# XXXX_468323_001_3.net
KiCad netlist of a schematic drawn in Altium Designer
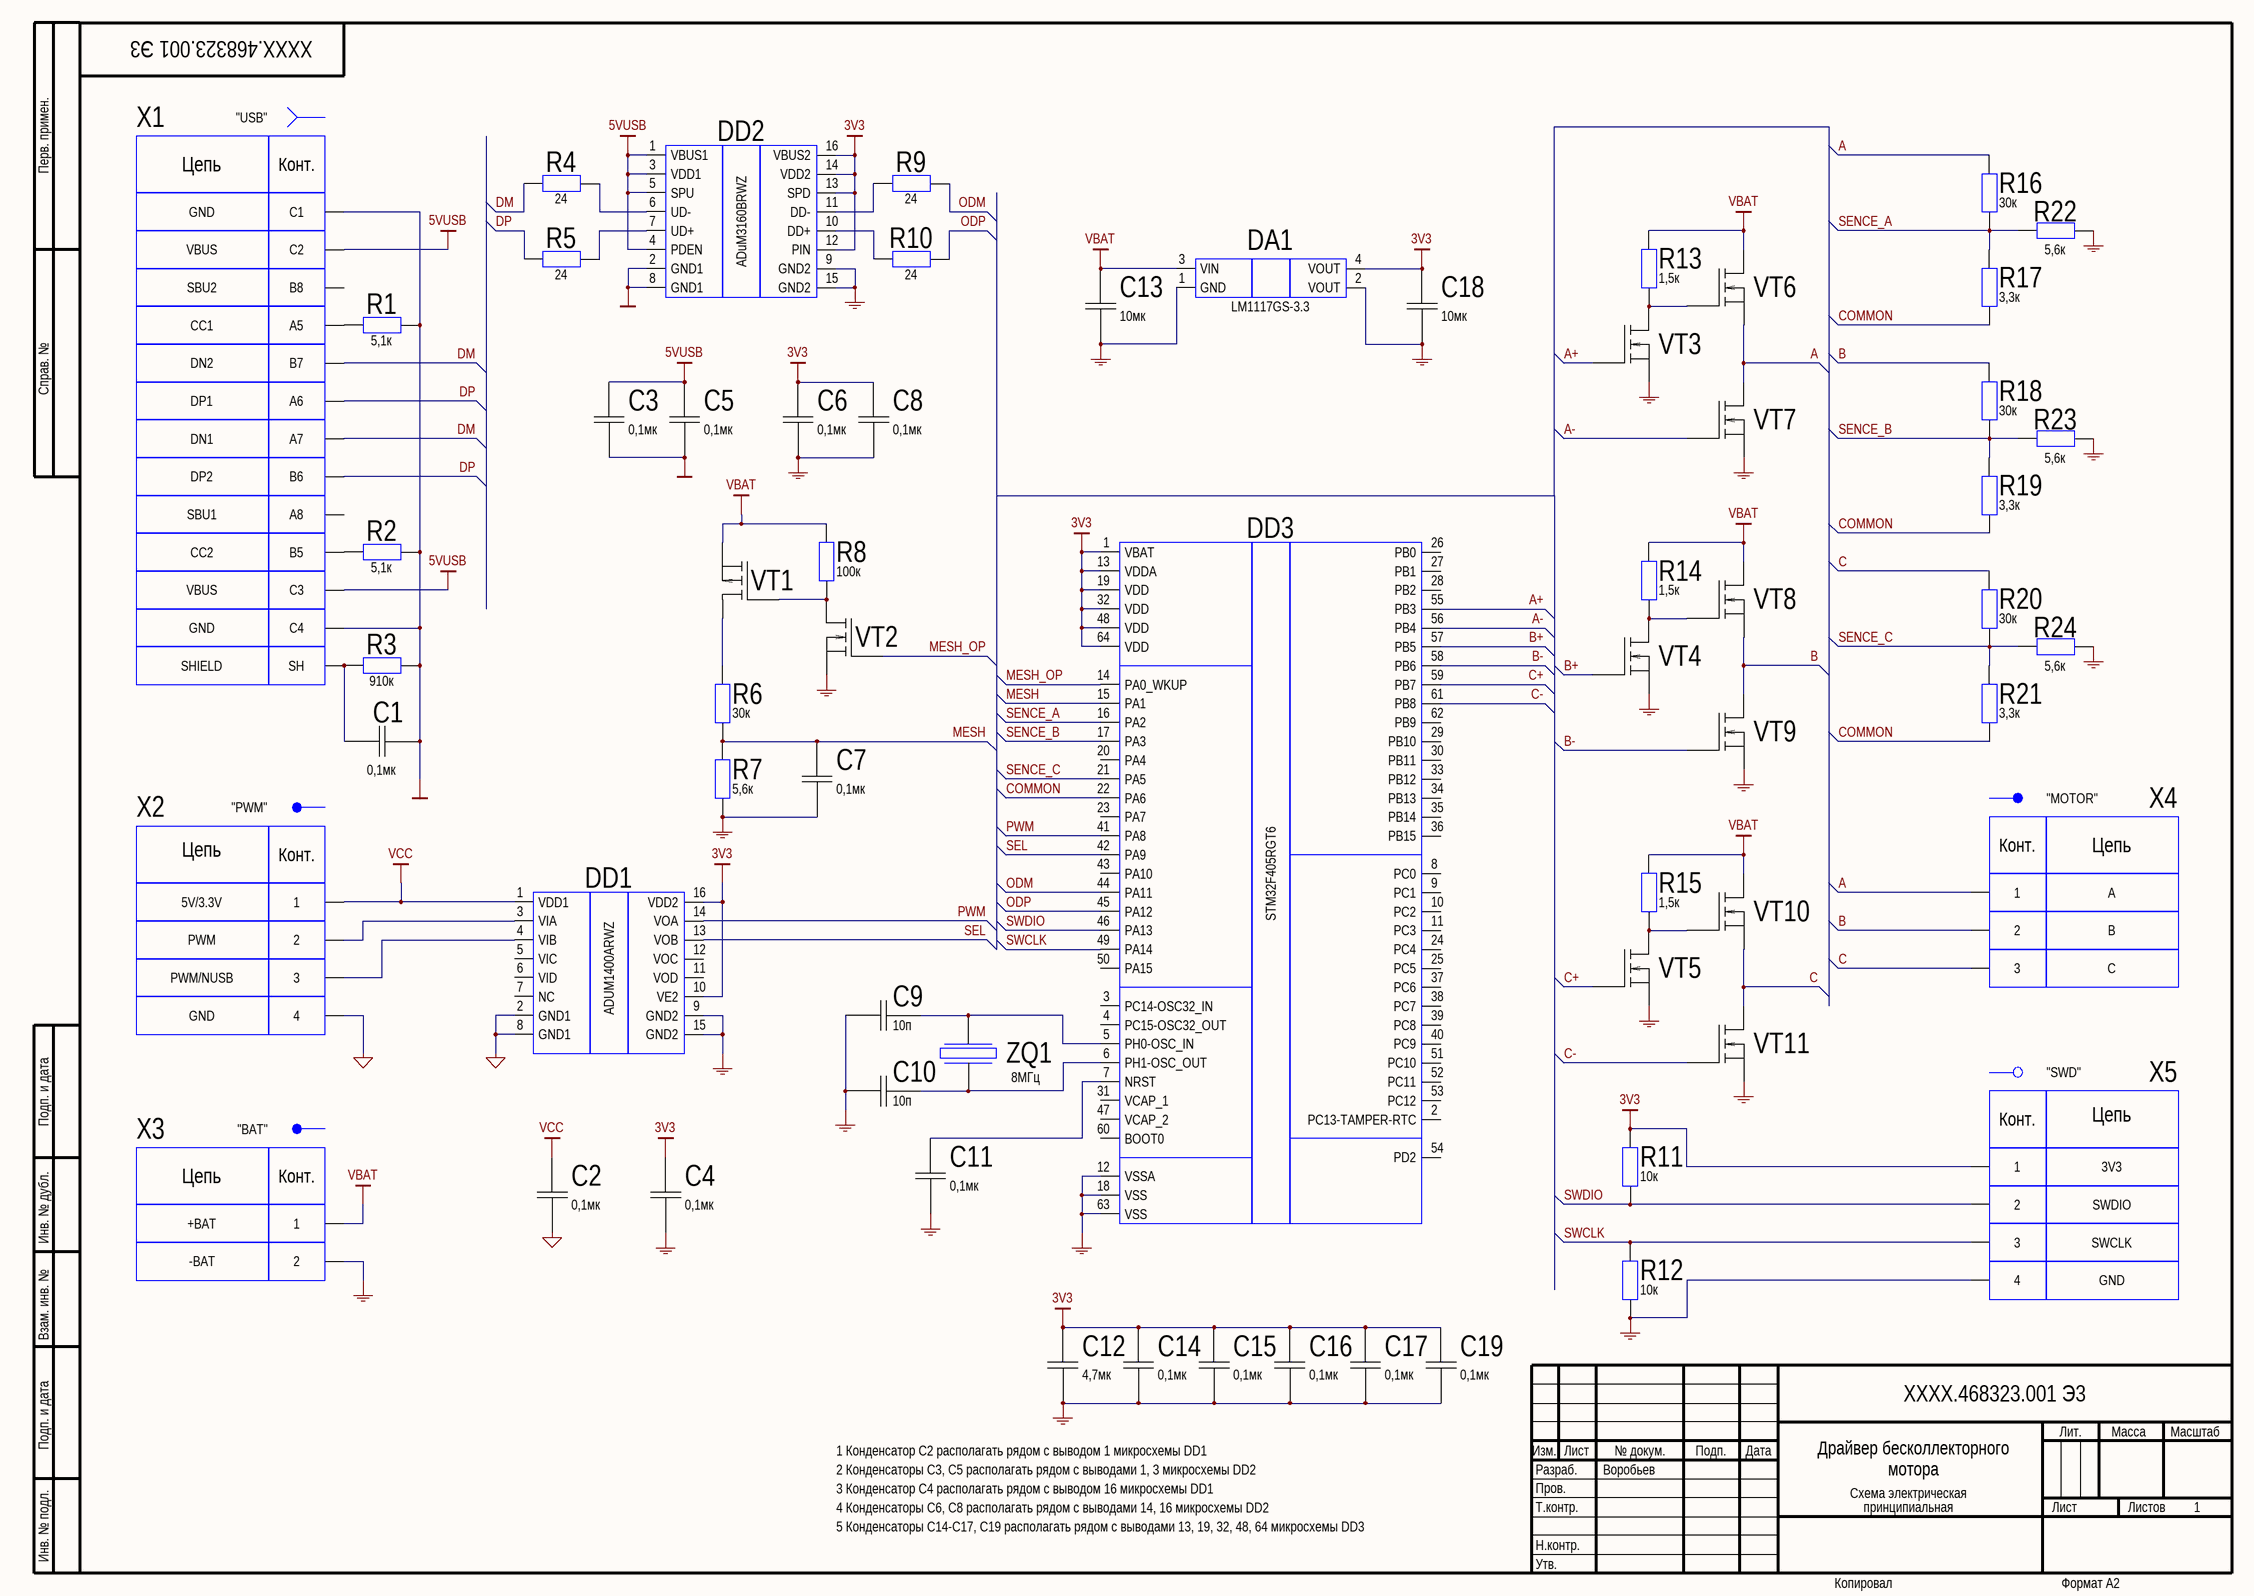
[diagram p0: XXXX.468323.001 Э3 Драйвер бесколлекторного мотора. Схема электрическая принципиальная.SchDoc]

(export (version "E")
  (design (tool "Eeschema 10.0.6"))
  (components
    (comp (ref "C1")
      (value "0,1мк")
      (footprint "CAPC1608X06L")
      (description "SMD0603 X7R 50 В, 0,1мкФ±10% CC0603KRX7R9BB104")
      (fields (field (name "PART NUMBER") "CC0603KRX7R9BB104") (field (name "VOLTAGE") "50 В"))
      (libsource (lib "Capacitors") (part "CAP"))
    )
    (comp (ref "C2")
      (value "0,1мк")
      (footprint "CAPC1608X06L")
      (description "SMD0603 X7R 50 В, 0,1мкФ±10% CC0603KRX7R9BB104")
      (fields (field (name "PART NUMBER") "CC0603KRX7R9BB104") (field (name "VOLTAGE") "50 В"))
      (libsource (lib "Capacitors") (part "CAP"))
    )
    (comp (ref "C3")
      (value "0,1мк")
      (footprint "CAPC1608X06L")
      (description "SMD0603 X7R 50 В, 0,1мкФ±10% CC0603KRX7R9BB104")
      (fields (field (name "PART NUMBER") "CC0603KRX7R9BB104") (field (name "VOLTAGE") "50 В"))
      (libsource (lib "Capacitors") (part "CAP"))
    )
    (comp (ref "C4")
      (value "0,1мк")
      (footprint "CAPC1608X06L")
      (description "SMD0603 X7R 50 В, 0,1мкФ±10% CC0603KRX7R9BB104")
      (fields (field (name "PART NUMBER") "CC0603KRX7R9BB104") (field (name "VOLTAGE") "50 В"))
      (libsource (lib "Capacitors") (part "CAP"))
    )
    (comp (ref "C5")
      (value "0,1мк")
      (footprint "CAPC1608X06L")
      (description "SMD0603 X7R 50 В, 0,1мкФ±10% CC0603KRX7R9BB104")
      (fields (field (name "PART NUMBER") "CC0603KRX7R9BB104") (field (name "VOLTAGE") "50 В"))
      (libsource (lib "Capacitors") (part "CAP"))
    )
    (comp (ref "C6")
      (value "0,1мк")
      (footprint "CAPC1608X06L")
      (description "SMD0603 X7R 50 В, 0,1мкФ±10% CC0603KRX7R9BB104")
      (fields (field (name "PART NUMBER") "CC0603KRX7R9BB104") (field (name "VOLTAGE") "50 В"))
      (libsource (lib "Capacitors") (part "CAP"))
    )
    (comp (ref "C7")
      (value "0,1мк")
      (footprint "CAPC1608X06L")
      (description "SMD0603 X7R 50 В, 0,1мкФ±10% CC0603KRX7R9BB104")
      (fields (field (name "PART NUMBER") "CC0603KRX7R9BB104") (field (name "VOLTAGE") "50 В"))
      (libsource (lib "Capacitors") (part "CAP"))
    )
    (comp (ref "C8")
      (value "0,1мк")
      (footprint "CAPC1608X06L")
      (description "SMD0603 X7R 50 В, 0,1мкФ±10% CC0603KRX7R9BB104")
      (fields (field (name "PART NUMBER") "CC0603KRX7R9BB104") (field (name "VOLTAGE") "50 В"))
      (libsource (lib "Capacitors") (part "CAP"))
    )
    (comp (ref "C9")
      (value "10п")
      (footprint "CAPC1608X06L")
      (description "SMD0603 NPO 50 В, 10пФ±5% CC0603JRNPO9BN100")
      (fields (field (name "PART NUMBER") "CC0603JRNPO9BN100") (field (name "VOLTAGE") "50 В"))
      (libsource (lib "Capacitors") (part "CAP"))
    )
    (comp (ref "C10")
      (value "10п")
      (footprint "CAPC1608X06L")
      (description "SMD0603 NPO 50 В, 10пФ±5% CC0603JRNPO9BN100")
      (fields (field (name "PART NUMBER") "CC0603JRNPO9BN100") (field (name "VOLTAGE") "50 В"))
      (libsource (lib "Capacitors") (part "CAP"))
    )
    (comp (ref "C11")
      (value "0,1мк")
      (footprint "CAPC1608X06L")
      (description "SMD0603 X7R 50 В, 0,1мкФ±10% CC0603KRX7R9BB104")
      (fields (field (name "PART NUMBER") "CC0603KRX7R9BB104") (field (name "VOLTAGE") "50 В"))
      (libsource (lib "Capacitors") (part "CAP"))
    )
    (comp (ref "C12")
      (value "4,7мк")
      (footprint "CAPC1608X06L")
      (description "SMD0603 X5R 6,3 В, 4,7мкФ±10% CC0603KRX5R5BB475")
      (fields (field (name "PART NUMBER") "CC0603KRX5R5BB475") (field (name "VOLTAGE") "6,3 В"))
      (libsource (lib "Capacitors") (part "CAP"))
    )
    (comp (ref "C13")
      (value "10мк")
      (footprint "CAPC3225X28N")
      (description "SMD1210 Y5R 50 В, 10мкФ±-20/+80% CC1210ZKY5V9BB106")
      (fields (field (name "PART NUMBER") "CC1210ZKY5V9BB106") (field (name "VOLTAGE") "50 В"))
      (libsource (lib "Capacitors") (part "CAP"))
    )
    (comp (ref "C14")
      (value "0,1мк")
      (footprint "CAPC1608X06L")
      (description "SMD0603 X7R 50 В, 0,1мкФ±10% CC0603KRX7R9BB104")
      (fields (field (name "PART NUMBER") "CC0603KRX7R9BB104") (field (name "VOLTAGE") "50 В"))
      (libsource (lib "Capacitors") (part "CAP"))
    )
    (comp (ref "C15")
      (value "0,1мк")
      (footprint "CAPC1608X06L")
      (description "SMD0603 X7R 50 В, 0,1мкФ±10% CC0603KRX7R9BB104")
      (fields (field (name "PART NUMBER") "CC0603KRX7R9BB104") (field (name "VOLTAGE") "50 В"))
      (libsource (lib "Capacitors") (part "CAP"))
    )
    (comp (ref "C16")
      (value "0,1мк")
      (footprint "CAPC1608X06L")
      (description "SMD0603 X7R 50 В, 0,1мкФ±10% CC0603KRX7R9BB104")
      (fields (field (name "PART NUMBER") "CC0603KRX7R9BB104") (field (name "VOLTAGE") "50 В"))
      (libsource (lib "Capacitors") (part "CAP"))
    )
    (comp (ref "C17")
      (value "0,1мк")
      (footprint "CAPC1608X06L")
      (description "SMD0603 X7R 50 В, 0,1мкФ±10% CC0603KRX7R9BB104")
      (fields (field (name "PART NUMBER") "CC0603KRX7R9BB104") (field (name "VOLTAGE") "50 В"))
      (libsource (lib "Capacitors") (part "CAP"))
    )
    (comp (ref "C18")
      (value "10мк")
      (footprint "CAPC1608X06L")
      (description "SMD0603 X5R 10 В, 10мкФ±10% CC0603KRX5R6BB106")
      (fields (field (name "PART NUMBER") "CC0603KRX5R6BB106") (field (name "VOLTAGE") "10 В"))
      (libsource (lib "Capacitors") (part "CAP"))
    )
    (comp (ref "C19")
      (value "0,1мк")
      (footprint "CAPC1608X06L")
      (description "SMD0603 X7R 50 В, 0,1мкФ±10% CC0603KRX7R9BB104")
      (fields (field (name "PART NUMBER") "CC0603KRX7R9BB104") (field (name "VOLTAGE") "50 В"))
      (libsource (lib "Capacitors") (part "CAP"))
    )
    (comp (ref "DA1")
      (value "LM1117GS-3.3")
      (footprint "SOT230P700X180-4N")
      (libsource (lib "IC") (part "LM1117GS-3.3"))
    )
    (comp (ref "DD1")
      (value "ADUM1400ARWZ")
      (footprint "SOP127P1030X265-16N")
      (libsource (lib "IC") (part "ADuM1400"))
    )
    (comp (ref "DD2")
      (value "ADuM3160BRWZ")
      (footprint "SOP127P1030X265-16N")
      (libsource (lib "IC") (part "ADuM3160"))
    )
    (comp (ref "DD3")
      (value "STM32F405RGT6")
      (footprint "TSQFP50P1200X1200X160-64N")
      (libsource (lib "IC") (part "STM32F405Rx"))
    )
    (comp (ref "R1")
      (value "5,1к")
      (footprint "RESC1608X06M")
      (description "SMD0603 0,1 Вт, 5,1 кОм±1% RC0603FR-075K1L")
      (fields (field (name "PART NUMBER") "RC0603FR-075K1L") (field (name "TOLERANCE") "1%"))
      (libsource (lib "") (part "RES_1"))
    )
    (comp (ref "R2")
      (value "5,1к")
      (footprint "RESC1608X06M")
      (description "SMD0603 0,1 Вт, 5,1 кОм±1% RC0603FR-075K1L")
      (fields (field (name "PART NUMBER") "RC0603FR-075K1L") (field (name "TOLERANCE") "1%"))
      (libsource (lib "") (part "RES_1"))
    )
    (comp (ref "R3")
      (value "910к")
      (footprint "RESC1608X06M")
      (description "SMD0603 0,1 Вт, 910 кОм±1% RC0603FR-07910KL")
      (fields (field (name "PART NUMBER") "RC0603FR-07910KL") (field (name "TOLERANCE") "1%"))
      (libsource (lib "") (part "RES_1"))
    )
    (comp (ref "R4")
      (value "24")
      (footprint "RESC1608X06M")
      (description "SMD0603 0,1 Вт, 24 Ом±1% RC0603FR-0724RL")
      (fields (field (name "PART NUMBER") "RC0603FR-0724RL") (field (name "TOLERANCE") "1%"))
      (libsource (lib "") (part "RES_1"))
    )
    (comp (ref "R5")
      (value "24")
      (footprint "RESC1608X06M")
      (description "SMD0603 0,1 Вт, 24 Ом±1% RC0603FR-0724RL")
      (fields (field (name "PART NUMBER") "RC0603FR-0724RL") (field (name "TOLERANCE") "1%"))
      (libsource (lib "") (part "RES_1"))
    )
    (comp (ref "R6")
      (value "30к")
      (footprint "RESC1608X06M")
      (description "SMD0603 0,1 Вт, 30 кОм±1% RC0603FR-0730KL")
      (fields (field (name "PART NUMBER") "RC0603FR-0730KL") (field (name "TOLERANCE") "1%"))
      (libsource (lib "") (part "RES_2"))
    )
    (comp (ref "R7")
      (value "5,6к")
      (footprint "RESC1608X06M")
      (description "SMD0603 0,1 Вт, 5,6 кОм±1% RC0603FR-075K6L")
      (fields (field (name "PART NUMBER") "RC0603FR-075K6L") (field (name "TOLERANCE") "1%"))
      (libsource (lib "") (part "RES_2"))
    )
    (comp (ref "R8")
      (value "100к")
      (footprint "RESC1608X06M")
      (description "SMD0603 0,1 Вт, 100 кОм±1% RC0603FR-07100KL")
      (fields (field (name "PART NUMBER") "RC0603FR-07100KL") (field (name "TOLERANCE") "1%"))
      (libsource (lib "") (part "RES_2"))
    )
    (comp (ref "R9")
      (value "24")
      (footprint "RESC1608X06M")
      (description "SMD0603 0,1 Вт, 24 Ом±1% RC0603FR-0724RL")
      (fields (field (name "PART NUMBER") "RC0603FR-0724RL") (field (name "TOLERANCE") "1%"))
      (libsource (lib "") (part "RES_1"))
    )
    (comp (ref "R10")
      (value "24")
      (footprint "RESC1608X06M")
      (description "SMD0603 0,1 Вт, 24 Ом±1% RC0603FR-0724RL")
      (fields (field (name "PART NUMBER") "RC0603FR-0724RL") (field (name "TOLERANCE") "1%"))
      (libsource (lib "") (part "RES_1"))
    )
    (comp (ref "R11")
      (value "10к")
      (footprint "RESC1608X06M")
      (description "SMD0603 0,1 Вт, 10 кОм±1% RC0603FR-0710KL")
      (fields (field (name "PART NUMBER") "RC0603FR-0710KL") (field (name "TOLERANCE") "1%"))
      (libsource (lib "") (part "RES_2"))
    )
    (comp (ref "R12")
      (value "10к")
      (footprint "RESC1608X06M")
      (description "SMD0603 0,1 Вт, 10 кОм±1% RC0603FR-0710KL")
      (fields (field (name "PART NUMBER") "RC0603FR-0710KL") (field (name "TOLERANCE") "1%"))
      (libsource (lib "") (part "RES_2"))
    )
    (comp (ref "R13")
      (value "1,5к")
      (footprint "RESC1608X06M")
      (description "SMD0603 0,1 Вт, 1,5 кОм±1% RC0603FR-071K5L")
      (fields (field (name "PART NUMBER") "RC0603FR-071K5L") (field (name "TOLERANCE") "1%"))
      (libsource (lib "") (part "RES_2"))
    )
    (comp (ref "R14")
      (value "1,5к")
      (footprint "RESC1608X06M")
      (description "SMD0603 0,1 Вт, 1,5 кОм±1% RC0603FR-071K5L")
      (fields (field (name "PART NUMBER") "RC0603FR-071K5L") (field (name "TOLERANCE") "1%"))
      (libsource (lib "") (part "RES_2"))
    )
    (comp (ref "R15")
      (value "1,5к")
      (footprint "RESC1608X06M")
      (description "SMD0603 0,1 Вт, 1,5 кОм±1% RC0603FR-071K5L")
      (fields (field (name "PART NUMBER") "RC0603FR-071K5L") (field (name "TOLERANCE") "1%"))
      (libsource (lib "") (part "RES_2"))
    )
    (comp (ref "R16")
      (value "30к")
      (footprint "RESC1608X06M")
      (description "SMD0603 0,1 Вт, 30 кОм±1% RC0603FR-0730KL")
      (fields (field (name "PART NUMBER") "RC0603FR-0730KL") (field (name "TOLERANCE") "1%"))
      (libsource (lib "") (part "RES_2"))
    )
    (comp (ref "R17")
      (value "3,3к")
      (footprint "RESC1608X06M")
      (description "SMD0603 0,1 Вт, 3,3 кОм±1% RC0603FR-073K3L")
      (fields (field (name "PART NUMBER") "RC0603FR-073K3L") (field (name "TOLERANCE") "1%"))
      (libsource (lib "") (part "RES_2"))
    )
    (comp (ref "R18")
      (value "30к")
      (footprint "RESC1608X06M")
      (description "SMD0603 0,1 Вт, 30 кОм±1% RC0603FR-0730KL")
      (fields (field (name "PART NUMBER") "RC0603FR-0730KL") (field (name "TOLERANCE") "1%"))
      (libsource (lib "") (part "RES_2"))
    )
    (comp (ref "R19")
      (value "3,3к")
      (footprint "RESC1608X06M")
      (description "SMD0603 0,1 Вт, 3,3 кОм±1% RC0603FR-073K3L")
      (fields (field (name "PART NUMBER") "RC0603FR-073K3L") (field (name "TOLERANCE") "1%"))
      (libsource (lib "") (part "RES_2"))
    )
    (comp (ref "R20")
      (value "30к")
      (footprint "RESC1608X06M")
      (description "SMD0603 0,1 Вт, 30 кОм±1% RC0603FR-0730KL")
      (fields (field (name "PART NUMBER") "RC0603FR-0730KL") (field (name "TOLERANCE") "1%"))
      (libsource (lib "") (part "RES_2"))
    )
    (comp (ref "R21")
      (value "3,3к")
      (footprint "RESC1608X06M")
      (description "SMD0603 0,1 Вт, 3,3 кОм±1% RC0603FR-073K3L")
      (fields (field (name "PART NUMBER") "RC0603FR-073K3L") (field (name "TOLERANCE") "1%"))
      (libsource (lib "") (part "RES_2"))
    )
    (comp (ref "R22")
      (value "5,6к")
      (footprint "RESC1608X06M")
      (description "SMD0603 0,1 Вт, 5,6 кОм±1% RC0603FR-075K6L")
      (fields (field (name "PART NUMBER") "RC0603FR-075K6L") (field (name "TOLERANCE") "1%"))
      (libsource (lib "Resistors") (part "RES"))
    )
    (comp (ref "R23")
      (value "5,6к")
      (footprint "RESC1608X06M")
      (description "SMD0603 0,1 Вт, 5,6 кОм±1% RC0603FR-075K6L")
      (fields (field (name "PART NUMBER") "RC0603FR-075K6L") (field (name "TOLERANCE") "1%"))
      (libsource (lib "Resistors") (part "RES"))
    )
    (comp (ref "R24")
      (value "5,6к")
      (footprint "RESC1608X06M")
      (description "SMD0603 0,1 Вт, 5,6 кОм±1% RC0603FR-075K6L")
      (fields (field (name "PART NUMBER") "RC0603FR-075K6L") (field (name "TOLERANCE") "1%"))
      (libsource (lib "Resistors") (part "RES"))
    )
    (comp (ref "VT1")
      (value "AO3401A")
      (footprint "SOT95P240X115-3N")
      (libsource (lib "Transistors") (part "AO3401A"))
    )
    (comp (ref "VT2")
      (value "IRLML0040TRPBF")
      (footprint "SOT95P240X115-3N")
      (libsource (lib "Transistors") (part "IRLML0040TRPBF"))
    )
    (comp (ref "VT3")
      (value "IRLML0040TRPBF")
      (footprint "SOT95P240X115-3N")
      (libsource (lib "Transistors") (part "IRLML0040TRPBF"))
    )
    (comp (ref "VT4")
      (value "IRLML0040TRPBF")
      (footprint "SOT95P240X115-3N")
      (libsource (lib "Transistors") (part "IRLML0040TRPBF"))
    )
    (comp (ref "VT5")
      (value "IRLML0040TRPBF")
      (footprint "SOT95P240X115-3N")
      (libsource (lib "Transistors") (part "IRLML0040TRPBF"))
    )
    (comp (ref "VT6")
      (value "P0603BD")
      (footprint "DPAK228P966X250-3N")
      (libsource (lib "Transistors") (part "P0603BD"))
    )
    (comp (ref "VT7")
      (value "P0603BD")
      (footprint "DPAK228P966X250-3N")
      (libsource (lib "Transistors") (part "P0603BD"))
    )
    (comp (ref "VT8")
      (value "P0603BD")
      (footprint "DPAK228P966X250-3N")
      (libsource (lib "Transistors") (part "P0603BD"))
    )
    (comp (ref "VT9")
      (value "P0603BD")
      (footprint "DPAK228P966X250-3N")
      (libsource (lib "Transistors") (part "P0603BD"))
    )
    (comp (ref "VT10")
      (value "P0603BD")
      (footprint "DPAK228P966X250-3N")
      (libsource (lib "Transistors") (part "P0603BD"))
    )
    (comp (ref "VT11")
      (value "P0603BD")
      (footprint "DPAK228P966X250-3N")
      (libsource (lib "Transistors") (part "P0603BD"))
    )
    (comp (ref "X1")
      (value "\"USB\"")
      (footprint "USB3.1 TYPE-C 16PF-015")
      (description "Разъём USB Type C USB3.1 TYPE-C 16PF-015")
      (fields (field (name "PART NUMBER") "USB3.1 TYPE-C 16PF-015"))
      (libsource (lib "Connectors") (part "USB3.1 TYPE-C 16PF-015"))
    )
    (comp (ref "X2")
      (value "\"PWM\"")
      (footprint "Pads 4x2.54")
      (fields
        (field (name "NETNAME4") "GND")
        (field (name "NETNAME3") "PWM/NUSB")
        (field (name "NETNAME2") "PWM")
        (field (name "NETNAME1") "5V/3.3V")
        (field (name "PART NUMBER") "pads 4x2,54")
      )
      (libsource (lib "Connectors") (part "CONNECTOR_4PIN"))
    )
    (comp (ref "X3")
      (value "\"BAT\"")
      (footprint "Pads 2x2.54")
      (fields
        (field (name "NETNAME2") "-BAT")
        (field (name "NETNAME1") "+BAT")
        (field (name "PART NUMBER") "pads 2x2,54")
      )
      (libsource (lib "Connectors") (part "CONNECTOR_2PIN"))
    )
    (comp (ref "X4")
      (value "\"MOTOR\"")
      (footprint "Pads 3x2.54")
      (fields
        (field (name "NETNAME3") "C")
        (field (name "NETNAME2") "B")
        (field (name "NETNAME1") "A")
        (field (name "PART NUMBER") "pads 3x2,54")
      )
      (libsource (lib "Connectors") (part "CONNECTOR_3PIN"))
    )
    (comp (ref "X5")
      (value "\"SWD\"")
      (footprint "Pads 4x2.54")
      (fields
        (field (name "NETNAME4") "GND")
        (field (name "NETNAME3") "SWCLK")
        (field (name "NETNAME2") "SWDIO")
        (field (name "NETNAME1") "3V3")
        (field (name "PART NUMBER") "pads 4x2,54")
      )
      (libsource (lib "") (part "CONNECTOR_4PIN_1"))
    )
    (comp (ref "ZQ1")
      (value "8МГц")
      (footprint "HC49/S")
      (fields (field (name "PART NUMBER") "L-KLS14-HC-49S-8.000-16-30-C"))
      (libsource (lib "Resonators") (part "Resonator"))
    )
  )
  (nets
    (net (code "1") (name "/A") (class "Default")
      (node (ref "R16") (pin "2") (pinfunction "2_2") (pintype "passive"))
      (node (ref "VT6") (pin "3") (pinfunction "S_3") (pintype "passive"))
      (node (ref "VT7") (pin "4") (pinfunction "D_4") (pintype "passive"))
      (node (ref "X4") (pin "1") (pinfunction "1_1") (pintype "passive"))
    )
    (net (code "2") (name "/A+") (class "Default")
      (node (ref "DD3") (pin "55") (pinfunction "PB3_55") (pintype "passive"))
      (node (ref "VT3") (pin "1") (pinfunction "G_1") (pintype "passive"))
    )
    (net (code "3") (name "/A-") (class "Default")
      (node (ref "DD3") (pin "56") (pinfunction "PB4_56") (pintype "passive"))
      (node (ref "VT7") (pin "1") (pinfunction "G_1") (pintype "passive"))
    )
    (net (code "4") (name "/B") (class "Default")
      (node (ref "R18") (pin "2") (pinfunction "2_2") (pintype "passive"))
      (node (ref "VT8") (pin "3") (pinfunction "S_3") (pintype "passive"))
      (node (ref "VT9") (pin "4") (pinfunction "D_4") (pintype "passive"))
      (node (ref "X4") (pin "2") (pinfunction "2_2") (pintype "passive"))
    )
    (net (code "5") (name "/B+") (class "Default")
      (node (ref "DD3") (pin "57") (pinfunction "PB5_57") (pintype "passive"))
      (node (ref "VT4") (pin "1") (pinfunction "G_1") (pintype "passive"))
    )
    (net (code "6") (name "/B-") (class "Default")
      (node (ref "DD3") (pin "58") (pinfunction "PB6_58") (pintype "passive"))
      (node (ref "VT9") (pin "1") (pinfunction "G_1") (pintype "passive"))
    )
    (net (code "7") (name "/C") (class "Default")
      (node (ref "R20") (pin "2") (pinfunction "2_2") (pintype "passive"))
      (node (ref "VT10") (pin "3") (pinfunction "S_3") (pintype "passive"))
      (node (ref "VT11") (pin "4") (pinfunction "D_4") (pintype "passive"))
      (node (ref "X4") (pin "3") (pinfunction "3_3") (pintype "passive"))
    )
    (net (code "8") (name "/C+") (class "Default")
      (node (ref "DD3") (pin "59") (pinfunction "PB7_59") (pintype "passive"))
      (node (ref "VT5") (pin "1") (pinfunction "G_1") (pintype "passive"))
    )
    (net (code "9") (name "/C-") (class "Default")
      (node (ref "DD3") (pin "61") (pinfunction "PB8_61") (pintype "passive"))
      (node (ref "VT11") (pin "1") (pinfunction "G_1") (pintype "passive"))
    )
    (net (code "10") (name "/COMMON") (class "Default")
      (node (ref "DD3") (pin "22") (pinfunction "PA6_22") (pintype "passive"))
      (node (ref "R17") (pin "1") (pinfunction "1_1") (pintype "passive"))
      (node (ref "R19") (pin "1") (pinfunction "1_1") (pintype "passive"))
      (node (ref "R21") (pin "1") (pinfunction "1_1") (pintype "passive"))
    )
    (net (code "11") (name "/DM") (class "Default")
      (node (ref "R4") (pin "1") (pinfunction "1_1") (pintype "passive"))
      (node (ref "X1") (pin "A7") (pintype "passive"))
      (node (ref "X1") (pin "B7") (pintype "passive"))
    )
    (net (code "12") (name "/DP") (class "Default")
      (node (ref "R5") (pin "1") (pinfunction "1_1") (pintype "passive"))
      (node (ref "X1") (pin "A6") (pintype "passive"))
      (node (ref "X1") (pin "B6") (pintype "passive"))
    )
    (net (code "13") (name "/MESH") (class "Default")
      (node (ref "C7") (pin "1") (pinfunction "1_1") (pintype "passive"))
      (node (ref "DD3") (pin "15") (pinfunction "PA1_15") (pintype "passive"))
      (node (ref "R6") (pin "1") (pinfunction "1_1") (pintype "passive"))
      (node (ref "R7") (pin "2") (pinfunction "2_2") (pintype "passive"))
    )
    (net (code "14") (name "/MESH_OP") (class "Default")
      (node (ref "DD3") (pin "14") (pinfunction "PA0_WKUP_14") (pintype "passive"))
      (node (ref "VT2") (pin "1") (pinfunction "G_1") (pintype "passive"))
    )
    (net (code "15") (name "/ODM") (class "Default")
      (node (ref "DD3") (pin "44") (pinfunction "PA11_44") (pintype "passive"))
      (node (ref "R9") (pin "2") (pinfunction "2_2") (pintype "passive"))
    )
    (net (code "16") (name "/ODP") (class "Default")
      (node (ref "DD3") (pin "45") (pinfunction "PA12_45") (pintype "passive"))
      (node (ref "R10") (pin "2") (pinfunction "2_2") (pintype "passive"))
    )
    (net (code "17") (name "/PWM") (class "Default")
      (node (ref "DD1") (pin "14") (pinfunction "VOA_14") (pintype "passive"))
      (node (ref "DD3") (pin "41") (pinfunction "PA8_41") (pintype "passive"))
    )
    (net (code "18") (name "/SEL") (class "Default")
      (node (ref "DD1") (pin "13") (pinfunction "VOB_13") (pintype "passive"))
      (node (ref "DD3") (pin "42") (pinfunction "PA9_42") (pintype "passive"))
    )
    (net (code "19") (name "/SENCE_A") (class "Default")
      (node (ref "DD3") (pin "16") (pinfunction "PA2_16") (pintype "passive"))
      (node (ref "R16") (pin "1") (pinfunction "1_1") (pintype "passive"))
      (node (ref "R17") (pin "2") (pinfunction "2_2") (pintype "passive"))
      (node (ref "R22") (pin "2") (pinfunction "2_2") (pintype "passive"))
    )
    (net (code "20") (name "/SENCE_B") (class "Default")
      (node (ref "DD3") (pin "17") (pinfunction "PA3_17") (pintype "passive"))
      (node (ref "R18") (pin "1") (pinfunction "1_1") (pintype "passive"))
      (node (ref "R19") (pin "2") (pinfunction "2_2") (pintype "passive"))
      (node (ref "R23") (pin "2") (pinfunction "2_2") (pintype "passive"))
    )
    (net (code "21") (name "/SENCE_C") (class "Default")
      (node (ref "DD3") (pin "21") (pinfunction "PA5_21") (pintype "passive"))
      (node (ref "R20") (pin "1") (pinfunction "1_1") (pintype "passive"))
      (node (ref "R21") (pin "2") (pinfunction "2_2") (pintype "passive"))
      (node (ref "R24") (pin "2") (pinfunction "2_2") (pintype "passive"))
    )
    (net (code "22") (name "/SWCLK") (class "Default")
      (node (ref "DD3") (pin "49") (pinfunction "PA14_49") (pintype "passive"))
      (node (ref "R12") (pin "2") (pinfunction "2_2") (pintype "passive"))
      (node (ref "X5") (pin "3") (pinfunction "3_3") (pintype "passive"))
    )
    (net (code "23") (name "/SWDIO") (class "Default")
      (node (ref "DD3") (pin "46") (pinfunction "PA13_46") (pintype "passive"))
      (node (ref "R11") (pin "1") (pinfunction "1_1") (pintype "passive"))
      (node (ref "X5") (pin "2") (pinfunction "2_2") (pintype "passive"))
    )
    (net (code "24") (name "3V3") (class "Default")
      (node (ref "C12") (pin "1") (pinfunction "1_1") (pintype "passive"))
      (node (ref "C14") (pin "1") (pinfunction "1_1") (pintype "passive"))
      (node (ref "C15") (pin "1") (pinfunction "1_1") (pintype "passive"))
      (node (ref "C16") (pin "1") (pinfunction "1_1") (pintype "passive"))
      (node (ref "C17") (pin "1") (pinfunction "1_1") (pintype "passive"))
      (node (ref "C18") (pin "1") (pinfunction "1_1") (pintype "passive"))
      (node (ref "C19") (pin "1") (pinfunction "1_1") (pintype "passive"))
      (node (ref "C4") (pin "1") (pinfunction "1_1") (pintype "passive"))
      (node (ref "C6") (pin "1") (pinfunction "1_1") (pintype "passive"))
      (node (ref "C8") (pin "1") (pinfunction "1_1") (pintype "passive"))
      (node (ref "DA1") (pin "4") (pinfunction "VOUT_4") (pintype "passive"))
      (node (ref "DD1") (pin "10") (pinfunction "VE2_10") (pintype "passive"))
      (node (ref "DD1") (pin "16") (pinfunction "VDD2_16") (pintype "passive"))
      (node (ref "DD2") (pin "12") (pinfunction "PIN_12") (pintype "passive"))
      (node (ref "DD2") (pin "13") (pinfunction "SPD_13") (pintype "passive"))
      (node (ref "DD2") (pin "14") (pinfunction "VDD2_14") (pintype "passive"))
      (node (ref "DD2") (pin "16") (pinfunction "VBUS2_16") (pintype "passive"))
      (node (ref "DD3") (pin "1") (pinfunction "VBAT_1") (pintype "passive"))
      (node (ref "DD3") (pin "13") (pinfunction "VDDA_13") (pintype "passive"))
      (node (ref "DD3") (pin "19") (pinfunction "VDD_19") (pintype "passive"))
      (node (ref "DD3") (pin "32") (pinfunction "VDD_32") (pintype "passive"))
      (node (ref "DD3") (pin "48") (pinfunction "VDD_48") (pintype "passive"))
      (node (ref "DD3") (pin "64") (pinfunction "VDD_64") (pintype "passive"))
      (node (ref "R11") (pin "2") (pinfunction "2_2") (pintype "passive"))
      (node (ref "X5") (pin "1") (pinfunction "1_1") (pintype "passive"))
    )
    (net (code "25") (name "5VUSB") (class "Default")
      (node (ref "C3") (pin "1") (pinfunction "1_1") (pintype "passive"))
      (node (ref "C5") (pin "1") (pinfunction "1_1") (pintype "passive"))
      (node (ref "DD2") (pin "1") (pinfunction "VBUS1_1") (pintype "passive"))
      (node (ref "DD2") (pin "3") (pinfunction "VDD1_3") (pintype "passive"))
      (node (ref "DD2") (pin "4") (pinfunction "PDEN_4") (pintype "passive"))
      (node (ref "DD2") (pin "5") (pinfunction "SPU_5") (pintype "passive"))
      (node (ref "X1") (pin "C2") (pintype "passive"))
      (node (ref "X1") (pin "C3") (pintype "passive"))
    )
    (net (code "26") (name "GND") (class "Default")
      (node (ref "C1") (pin "2") (pinfunction "2_2") (pintype "passive"))
      (node (ref "C10") (pin "1") (pinfunction "1_1") (pintype "passive"))
      (node (ref "C11") (pin "2") (pinfunction "2_2") (pintype "passive"))
      (node (ref "C12") (pin "2") (pinfunction "2_2") (pintype "passive"))
      (node (ref "C13") (pin "2") (pinfunction "2_2") (pintype "passive"))
      (node (ref "C14") (pin "2") (pinfunction "2_2") (pintype "passive"))
      (node (ref "C15") (pin "2") (pinfunction "2_2") (pintype "passive"))
      (node (ref "C16") (pin "2") (pinfunction "2_2") (pintype "passive"))
      (node (ref "C17") (pin "2") (pinfunction "2_2") (pintype "passive"))
      (node (ref "C18") (pin "2") (pinfunction "2_2") (pintype "passive"))
      (node (ref "C19") (pin "2") (pinfunction "2_2") (pintype "passive"))
      (node (ref "C2") (pin "2") (pinfunction "2_2") (pintype "passive"))
      (node (ref "C3") (pin "2") (pinfunction "2_2") (pintype "passive"))
      (node (ref "C4") (pin "2") (pinfunction "2_2") (pintype "passive"))
      (node (ref "C5") (pin "2") (pinfunction "2_2") (pintype "passive"))
      (node (ref "C6") (pin "2") (pinfunction "2_2") (pintype "passive"))
      (node (ref "C7") (pin "2") (pinfunction "2_2") (pintype "passive"))
      (node (ref "C8") (pin "2") (pinfunction "2_2") (pintype "passive"))
      (node (ref "C9") (pin "1") (pinfunction "1_1") (pintype "passive"))
      (node (ref "DA1") (pin "1") (pinfunction "GND_1") (pintype "passive"))
      (node (ref "DA1") (pin "2") (pinfunction "VOUT_2") (pintype "passive"))
      (node (ref "DD1") (pin "15") (pinfunction "GND2_15") (pintype "passive"))
      (node (ref "DD1") (pin "2") (pinfunction "GND1_2") (pintype "passive"))
      (node (ref "DD1") (pin "8") (pinfunction "GND1_8") (pintype "passive"))
      (node (ref "DD1") (pin "9") (pinfunction "GND2_9") (pintype "passive"))
      (node (ref "DD2") (pin "15") (pinfunction "GND2_15") (pintype "passive"))
      (node (ref "DD2") (pin "2") (pinfunction "GND1_2") (pintype "passive"))
      (node (ref "DD2") (pin "8") (pinfunction "GND1_8") (pintype "passive"))
      (node (ref "DD2") (pin "9") (pinfunction "GND2_9") (pintype "passive"))
      (node (ref "DD3") (pin "12") (pinfunction "VSSA_12") (pintype "passive"))
      (node (ref "DD3") (pin "18") (pinfunction "VSS_18") (pintype "passive"))
      (node (ref "DD3") (pin "63") (pinfunction "VSS_63") (pintype "passive"))
      (node (ref "R1") (pin "2") (pinfunction "2_2") (pintype "passive"))
      (node (ref "R12") (pin "1") (pinfunction "1_1") (pintype "passive"))
      (node (ref "R2") (pin "2") (pinfunction "2_2") (pintype "passive"))
      (node (ref "R22") (pin "1") (pinfunction "1_1") (pintype "passive"))
      (node (ref "R23") (pin "1") (pinfunction "1_1") (pintype "passive"))
      (node (ref "R24") (pin "1") (pinfunction "1_1") (pintype "passive"))
      (node (ref "R3") (pin "2") (pinfunction "2_2") (pintype "passive"))
      (node (ref "R7") (pin "1") (pinfunction "1_1") (pintype "passive"))
      (node (ref "VT11") (pin "3") (pinfunction "S_3") (pintype "passive"))
      (node (ref "VT2") (pin "2") (pinfunction "S_2") (pintype "passive"))
      (node (ref "VT3") (pin "2") (pinfunction "S_2") (pintype "passive"))
      (node (ref "VT4") (pin "2") (pinfunction "S_2") (pintype "passive"))
      (node (ref "VT5") (pin "2") (pinfunction "S_2") (pintype "passive"))
      (node (ref "VT7") (pin "3") (pinfunction "S_3") (pintype "passive"))
      (node (ref "VT9") (pin "3") (pinfunction "S_3") (pintype "passive"))
      (node (ref "X1") (pin "C1") (pintype "passive"))
      (node (ref "X1") (pin "C4") (pintype "passive"))
      (node (ref "X2") (pin "4") (pinfunction "4_4") (pintype "passive"))
      (node (ref "X3") (pin "2") (pinfunction "2_2") (pintype "passive"))
      (node (ref "X5") (pin "4") (pinfunction "4_4") (pintype "passive"))
    )
    (net (code "27") (name "Net-(C1-Pad1)") (class "Default")
      (node (ref "C1") (pin "1") (pinfunction "1_1") (pintype "passive"))
      (node (ref "R3") (pin "1") (pinfunction "1_1") (pintype "passive"))
      (node (ref "X1") (pin "SHIELD") (pintype "passive"))
    )
    (net (code "28") (name "Net-(DD1-VIA)") (class "Default")
      (node (ref "DD1") (pin "3") (pinfunction "VIA_3") (pintype "passive"))
      (node (ref "X2") (pin "2") (pinfunction "2_2") (pintype "passive"))
    )
    (net (code "29") (name "Net-(DD1-VIB)") (class "Default")
      (node (ref "DD1") (pin "4") (pinfunction "VIB_4") (pintype "passive"))
      (node (ref "X2") (pin "3") (pinfunction "3_3") (pintype "passive"))
    )
    (net (code "30") (name "Net-(DD2-DD+)") (class "Default")
      (node (ref "DD2") (pin "10") (pinfunction "DD+_10") (pintype "passive"))
      (node (ref "R10") (pin "1") (pinfunction "1_1") (pintype "passive"))
    )
    (net (code "31") (name "Net-(DD2-DD-)") (class "Default")
      (node (ref "DD2") (pin "11") (pinfunction "DD-_11") (pintype "passive"))
      (node (ref "R9") (pin "1") (pinfunction "1_1") (pintype "passive"))
    )
    (net (code "32") (name "Net-(DD2-UD+)") (class "Default")
      (node (ref "DD2") (pin "7") (pinfunction "UD+_7") (pintype "passive"))
      (node (ref "R5") (pin "2") (pinfunction "2_2") (pintype "passive"))
    )
    (net (code "33") (name "Net-(DD2-UD-)") (class "Default")
      (node (ref "DD2") (pin "6") (pinfunction "UD-_6") (pintype "passive"))
      (node (ref "R4") (pin "2") (pinfunction "2_2") (pintype "passive"))
    )
    (net (code "34") (name "Net-(DD3-NRST)") (class "Default")
      (node (ref "C11") (pin "1") (pinfunction "1_1") (pintype "passive"))
      (node (ref "DD3") (pin "7") (pinfunction "NRST_7") (pintype "passive"))
    )
    (net (code "35") (name "Net-(DD3-PH0-OSC_IN)") (class "Default")
      (node (ref "C9") (pin "2") (pinfunction "2_2") (pintype "passive"))
      (node (ref "DD3") (pin "5") (pinfunction "PH0-OSC_IN_5") (pintype "passive"))
      (node (ref "ZQ1") (pin "1") (pinfunction "1_1") (pintype "passive"))
    )
    (net (code "36") (name "Net-(DD3-PH1-OSC_OUT)") (class "Default")
      (node (ref "C10") (pin "2") (pinfunction "2_2") (pintype "passive"))
      (node (ref "DD3") (pin "6") (pinfunction "PH1-OSC_OUT_6") (pintype "passive"))
      (node (ref "ZQ1") (pin "2") (pinfunction "2_2") (pintype "passive"))
    )
    (net (code "37") (name "Net-(R1-Pad1)") (class "Default")
      (node (ref "R1") (pin "1") (pinfunction "1_1") (pintype "passive"))
      (node (ref "X1") (pin "A5") (pintype "passive"))
    )
    (net (code "38") (name "Net-(R2-Pad1)") (class "Default")
      (node (ref "R2") (pin "1") (pinfunction "1_1") (pintype "passive"))
      (node (ref "X1") (pin "B5") (pintype "passive"))
    )
    (net (code "39") (name "Net-(VT1-D)") (class "Default")
      (node (ref "R6") (pin "2") (pinfunction "2_2") (pintype "passive"))
      (node (ref "VT1") (pin "3") (pinfunction "D_3") (pintype "passive"))
    )
    (net (code "40") (name "Net-(VT1-G)") (class "Default")
      (node (ref "R8") (pin "1") (pinfunction "1_1") (pintype "passive"))
      (node (ref "VT1") (pin "1") (pinfunction "G_1") (pintype "passive"))
      (node (ref "VT2") (pin "3") (pinfunction "D_3") (pintype "passive"))
    )
    (net (code "41") (name "Net-(VT3-D)") (class "Default")
      (node (ref "R13") (pin "1") (pinfunction "1_1") (pintype "passive"))
      (node (ref "VT3") (pin "3") (pinfunction "D_3") (pintype "passive"))
      (node (ref "VT6") (pin "1") (pinfunction "G_1") (pintype "passive"))
    )
    (net (code "42") (name "Net-(VT4-D)") (class "Default")
      (node (ref "R14") (pin "1") (pinfunction "1_1") (pintype "passive"))
      (node (ref "VT4") (pin "3") (pinfunction "D_3") (pintype "passive"))
      (node (ref "VT8") (pin "1") (pinfunction "G_1") (pintype "passive"))
    )
    (net (code "43") (name "Net-(VT10-G)") (class "Default")
      (node (ref "R15") (pin "1") (pinfunction "1_1") (pintype "passive"))
      (node (ref "VT10") (pin "1") (pinfunction "G_1") (pintype "passive"))
      (node (ref "VT5") (pin "3") (pinfunction "D_3") (pintype "passive"))
    )
    (net (code "44") (name "VBAT") (class "Default")
      (node (ref "C13") (pin "1") (pinfunction "1_1") (pintype "passive"))
      (node (ref "DA1") (pin "3") (pinfunction "VIN_3") (pintype "passive"))
      (node (ref "R13") (pin "2") (pinfunction "2_2") (pintype "passive"))
      (node (ref "R14") (pin "2") (pinfunction "2_2") (pintype "passive"))
      (node (ref "R15") (pin "2") (pinfunction "2_2") (pintype "passive"))
      (node (ref "R8") (pin "2") (pinfunction "2_2") (pintype "passive"))
      (node (ref "VT1") (pin "2") (pinfunction "S_2") (pintype "passive"))
      (node (ref "VT10") (pin "4") (pinfunction "D_4") (pintype "passive"))
      (node (ref "VT6") (pin "4") (pinfunction "D_4") (pintype "passive"))
      (node (ref "VT8") (pin "4") (pinfunction "D_4") (pintype "passive"))
      (node (ref "X3") (pin "1") (pinfunction "1_1") (pintype "passive"))
    )
    (net (code "45") (name "VCC") (class "Default")
      (node (ref "C2") (pin "1") (pinfunction "1_1") (pintype "passive"))
      (node (ref "DD1") (pin "1") (pinfunction "VDD1_1") (pintype "passive"))
      (node (ref "X2") (pin "1") (pinfunction "1_1") (pintype "passive"))
    )
    (net (code "46") (name "unconnected-(DD1-NC-Pad7)") (class "Default")
      (node (ref "DD1") (pin "7") (pinfunction "NC_7") (pintype "passive"))
    )
    (net (code "47") (name "unconnected-(DD1-VIC-Pad5)") (class "Default")
      (node (ref "DD1") (pin "5") (pinfunction "VIC_5") (pintype "passive"))
    )
    (net (code "48") (name "unconnected-(DD1-VID-Pad6)") (class "Default")
      (node (ref "DD1") (pin "6") (pinfunction "VID_6") (pintype "passive"))
    )
    (net (code "49") (name "unconnected-(DD1-VOC-Pad12)") (class "Default")
      (node (ref "DD1") (pin "12") (pinfunction "VOC_12") (pintype "passive"))
    )
    (net (code "50") (name "unconnected-(DD1-VOD-Pad11)") (class "Default")
      (node (ref "DD1") (pin "11") (pinfunction "VOD_11") (pintype "passive"))
    )
    (net (code "51") (name "unconnected-(DD3-BOOT0-Pad60)") (class "Default")
      (node (ref "DD3") (pin "60") (pinfunction "BOOT0_60") (pintype "passive"))
    )
    (net (code "52") (name "unconnected-(DD3-PA4-Pad20)") (class "Default")
      (node (ref "DD3") (pin "20") (pinfunction "PA4_20") (pintype "passive"))
    )
    (net (code "53") (name "unconnected-(DD3-PA7-Pad23)") (class "Default")
      (node (ref "DD3") (pin "23") (pinfunction "PA7_23") (pintype "passive"))
    )
    (net (code "54") (name "unconnected-(DD3-PA10-Pad43)") (class "Default")
      (node (ref "DD3") (pin "43") (pinfunction "PA10_43") (pintype "passive"))
    )
    (net (code "55") (name "unconnected-(DD3-PA15-Pad50)") (class "Default")
      (node (ref "DD3") (pin "50") (pinfunction "PA15_50") (pintype "passive"))
    )
    (net (code "56") (name "unconnected-(DD3-PB0-Pad26)") (class "Default")
      (node (ref "DD3") (pin "26") (pinfunction "PB0_26") (pintype "passive"))
    )
    (net (code "57") (name "unconnected-(DD3-PB1-Pad27)") (class "Default")
      (node (ref "DD3") (pin "27") (pinfunction "PB1_27") (pintype "passive"))
    )
    (net (code "58") (name "unconnected-(DD3-PB2-Pad28)") (class "Default")
      (node (ref "DD3") (pin "28") (pinfunction "PB2_28") (pintype "passive"))
    )
    (net (code "59") (name "unconnected-(DD3-PB9-Pad62)") (class "Default")
      (node (ref "DD3") (pin "62") (pinfunction "PB9_62") (pintype "passive"))
    )
    (net (code "60") (name "unconnected-(DD3-PB10-Pad29)") (class "Default")
      (node (ref "DD3") (pin "29") (pinfunction "PB10_29") (pintype "passive"))
    )
    (net (code "61") (name "unconnected-(DD3-PB11-Pad30)") (class "Default")
      (node (ref "DD3") (pin "30") (pinfunction "PB11_30") (pintype "passive"))
    )
    (net (code "62") (name "unconnected-(DD3-PB12-Pad33)") (class "Default")
      (node (ref "DD3") (pin "33") (pinfunction "PB12_33") (pintype "passive"))
    )
    (net (code "63") (name "unconnected-(DD3-PB13-Pad34)") (class "Default")
      (node (ref "DD3") (pin "34") (pinfunction "PB13_34") (pintype "passive"))
    )
    (net (code "64") (name "unconnected-(DD3-PB14-Pad35)") (class "Default")
      (node (ref "DD3") (pin "35") (pinfunction "PB14_35") (pintype "passive"))
    )
    (net (code "65") (name "unconnected-(DD3-PB15-Pad36)") (class "Default")
      (node (ref "DD3") (pin "36") (pinfunction "PB15_36") (pintype "passive"))
    )
    (net (code "66") (name "unconnected-(DD3-PC0-Pad8)") (class "Default")
      (node (ref "DD3") (pin "8") (pinfunction "PC0_8") (pintype "passive"))
    )
    (net (code "67") (name "unconnected-(DD3-PC1-Pad9)") (class "Default")
      (node (ref "DD3") (pin "9") (pinfunction "PC1_9") (pintype "passive"))
    )
    (net (code "68") (name "unconnected-(DD3-PC2-Pad10)") (class "Default")
      (node (ref "DD3") (pin "10") (pinfunction "PC2_10") (pintype "passive"))
    )
    (net (code "69") (name "unconnected-(DD3-PC3-Pad11)") (class "Default")
      (node (ref "DD3") (pin "11") (pinfunction "PC3_11") (pintype "passive"))
    )
    (net (code "70") (name "unconnected-(DD3-PC4-Pad24)") (class "Default")
      (node (ref "DD3") (pin "24") (pinfunction "PC4_24") (pintype "passive"))
    )
    (net (code "71") (name "unconnected-(DD3-PC5-Pad25)") (class "Default")
      (node (ref "DD3") (pin "25") (pinfunction "PC5_25") (pintype "passive"))
    )
    (net (code "72") (name "unconnected-(DD3-PC6-Pad37)") (class "Default")
      (node (ref "DD3") (pin "37") (pinfunction "PC6_37") (pintype "passive"))
    )
    (net (code "73") (name "unconnected-(DD3-PC7-Pad38)") (class "Default")
      (node (ref "DD3") (pin "38") (pinfunction "PC7_38") (pintype "passive"))
    )
    (net (code "74") (name "unconnected-(DD3-PC8-Pad39)") (class "Default")
      (node (ref "DD3") (pin "39") (pinfunction "PC8_39") (pintype "passive"))
    )
    (net (code "75") (name "unconnected-(DD3-PC9-Pad40)") (class "Default")
      (node (ref "DD3") (pin "40") (pinfunction "PC9_40") (pintype "passive"))
    )
    (net (code "76") (name "unconnected-(DD3-PC10-Pad51)") (class "Default")
      (node (ref "DD3") (pin "51") (pinfunction "PC10_51") (pintype "passive"))
    )
    (net (code "77") (name "unconnected-(DD3-PC11-Pad52)") (class "Default")
      (node (ref "DD3") (pin "52") (pinfunction "PC11_52") (pintype "passive"))
    )
    (net (code "78") (name "unconnected-(DD3-PC12-Pad53)") (class "Default")
      (node (ref "DD3") (pin "53") (pinfunction "PC12_53") (pintype "passive"))
    )
    (net (code "79") (name "unconnected-(DD3-PC13-TAMPER-RTC-Pad2)") (class "Default")
      (node (ref "DD3") (pin "2") (pinfunction "PC13-TAMPER-RTC_2") (pintype "passive"))
    )
    (net (code "80") (name "unconnected-(DD3-PC14-OSC32_IN-Pad3)") (class "Default")
      (node (ref "DD3") (pin "3") (pinfunction "PC14-OSC32_IN_3") (pintype "passive"))
    )
    (net (code "81") (name "unconnected-(DD3-PC15-OSC32_OUT-Pad4)") (class "Default")
      (node (ref "DD3") (pin "4") (pinfunction "PC15-OSC32_OUT_4") (pintype "passive"))
    )
    (net (code "82") (name "unconnected-(DD3-PD2-Pad54)") (class "Default")
      (node (ref "DD3") (pin "54") (pinfunction "PD2_54") (pintype "passive"))
    )
    (net (code "83") (name "unconnected-(DD3-VCAP_1-Pad31)") (class "Default")
      (node (ref "DD3") (pin "31") (pinfunction "VCAP_1_31") (pintype "passive"))
    )
    (net (code "84") (name "unconnected-(DD3-VCAP_2-Pad47)") (class "Default")
      (node (ref "DD3") (pin "47") (pinfunction "VCAP_2_47") (pintype "passive"))
    )
    (net (code "85") (name "unconnected-(X1-PadA8)") (class "Default")
      (node (ref "X1") (pin "A8") (pintype "passive"))
    )
    (net (code "86") (name "unconnected-(X1-PadB8)") (class "Default")
      (node (ref "X1") (pin "B8") (pintype "passive"))
    )
  )
)
